# POWER.net
KiCad netlist of a schematic drawn in Altium Designer
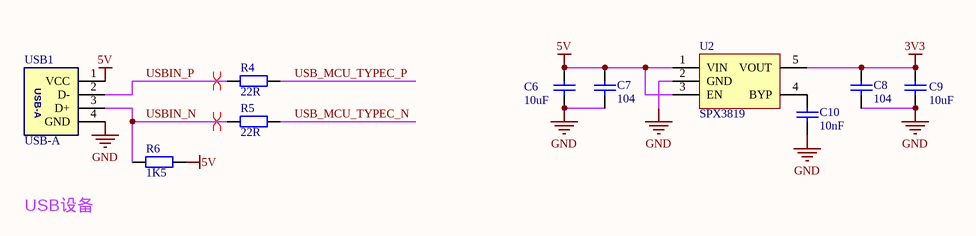
[diagram p0: POWER.SchDoc]

(export (version "E")
  (design (tool "Eeschema 10.0.6"))
  (components
    (comp (ref "C6")
      (value "10uF")
      (footprint "Cap-0603-M")
      (description "贴片陶瓷电容")
      (libsource (lib "Miscellaneous Base") (part "CAP"))
    )
    (comp (ref "C7")
      (value "104")
      (footprint "Cap-0402-M")
      (description "贴片陶瓷电容")
      (libsource (lib "Miscellaneous Base") (part "CAP"))
    )
    (comp (ref "C8")
      (value "104")
      (footprint "Cap-0402-M")
      (description "贴片陶瓷电容")
      (libsource (lib "Miscellaneous Base") (part "CAP"))
    )
    (comp (ref "C9")
      (value "10uF")
      (footprint "Cap-0603-M")
      (description "贴片陶瓷电容")
      (libsource (lib "Miscellaneous Base") (part "CAP"))
    )
    (comp (ref "C10")
      (value "10nF")
      (footprint "Cap-0402-M")
      (description "贴片陶瓷电容")
      (libsource (lib "Miscellaneous Base") (part "CAP"))
    )
    (comp (ref "R4")
      (value "22R")
      (footprint "Res-0402-M")
      (description "贴片电阻")
      (libsource (lib "Miscellaneous Base") (part "RES"))
    )
    (comp (ref "R5")
      (value "22R")
      (footprint "Res-0402-M")
      (description "贴片电阻")
      (libsource (lib "Miscellaneous Base") (part "RES"))
    )
    (comp (ref "R6")
      (value "1K5")
      (footprint "Res-0402-M")
      (description "贴片电阻")
      (libsource (lib "Miscellaneous Base") (part "RES"))
    )
    (comp (ref "U2")
      (value "SPX3819")
      (footprint "SOT23-5")
      (libsource (lib "Miscellaneous PMIC") (part "SPX3819"))
    )
    (comp (ref "USB1")
      (value "USB-A")
      (footprint "USB_A/P_B")
      (libsource (lib "Miscellaneous Socket") (part "USB-A"))
    )
  )
  (nets
    (net (code "1") (name "/USBIN_N") (class "Default")
      (node (ref "R5") (pin "1") (pinfunction "1_1") (pintype "passive"))
      (node (ref "R6") (pin "1") (pinfunction "1_1") (pintype "passive"))
      (node (ref "USB1") (pin "3") (pinfunction "D+_3") (pintype "passive"))
    )
    (net (code "2") (name "/USBIN_P") (class "Default")
      (node (ref "R4") (pin "1") (pinfunction "1_1") (pintype "passive"))
      (node (ref "USB1") (pin "2") (pinfunction "D-_2") (pintype "passive"))
    )
    (net (code "3") (name "/USB_MCU_TYPEC_N") (class "Default")
      (node (ref "R5") (pin "2") (pinfunction "2_2") (pintype "passive"))
    )
    (net (code "4") (name "/USB_MCU_TYPEC_P") (class "Default")
      (node (ref "R4") (pin "2") (pinfunction "2_2") (pintype "passive"))
    )
    (net (code "5") (name "3V3") (class "Default")
      (node (ref "C8") (pin "2") (pinfunction "2_2") (pintype "passive"))
      (node (ref "C9") (pin "2") (pinfunction "2_2") (pintype "passive"))
      (node (ref "U2") (pin "5") (pinfunction "VOUT_5") (pintype "power_in"))
    )
    (net (code "6") (name "5V") (class "Default")
      (node (ref "C6") (pin "2") (pinfunction "2_2") (pintype "passive"))
      (node (ref "C7") (pin "2") (pinfunction "2_2") (pintype "passive"))
      (node (ref "R6") (pin "2") (pinfunction "2_2") (pintype "passive"))
      (node (ref "U2") (pin "1") (pinfunction "VIN_1") (pintype "power_in"))
      (node (ref "U2") (pin "3") (pinfunction "EN_3") (pintype "power_in"))
      (node (ref "USB1") (pin "1") (pinfunction "VCC_1") (pintype "passive"))
    )
    (net (code "7") (name "GND") (class "Default")
      (node (ref "C10") (pin "1") (pinfunction "1_1") (pintype "passive"))
      (node (ref "C6") (pin "1") (pinfunction "1_1") (pintype "passive"))
      (node (ref "C7") (pin "1") (pinfunction "1_1") (pintype "passive"))
      (node (ref "C8") (pin "1") (pinfunction "1_1") (pintype "passive"))
      (node (ref "C9") (pin "1") (pinfunction "1_1") (pintype "passive"))
      (node (ref "U2") (pin "2") (pinfunction "GND_2") (pintype "power_in"))
      (node (ref "USB1") (pin "4") (pinfunction "GND_4") (pintype "passive"))
    )
    (net (code "8") (name "Net-(U2-BYP)") (class "Default")
      (node (ref "C10") (pin "2") (pinfunction "2_2") (pintype "passive"))
      (node (ref "U2") (pin "4") (pinfunction "BYP_4") (pintype "power_in"))
    )
  )
)
